# FE_Channel.net
KiCad netlist of a schematic drawn in Altium Designer
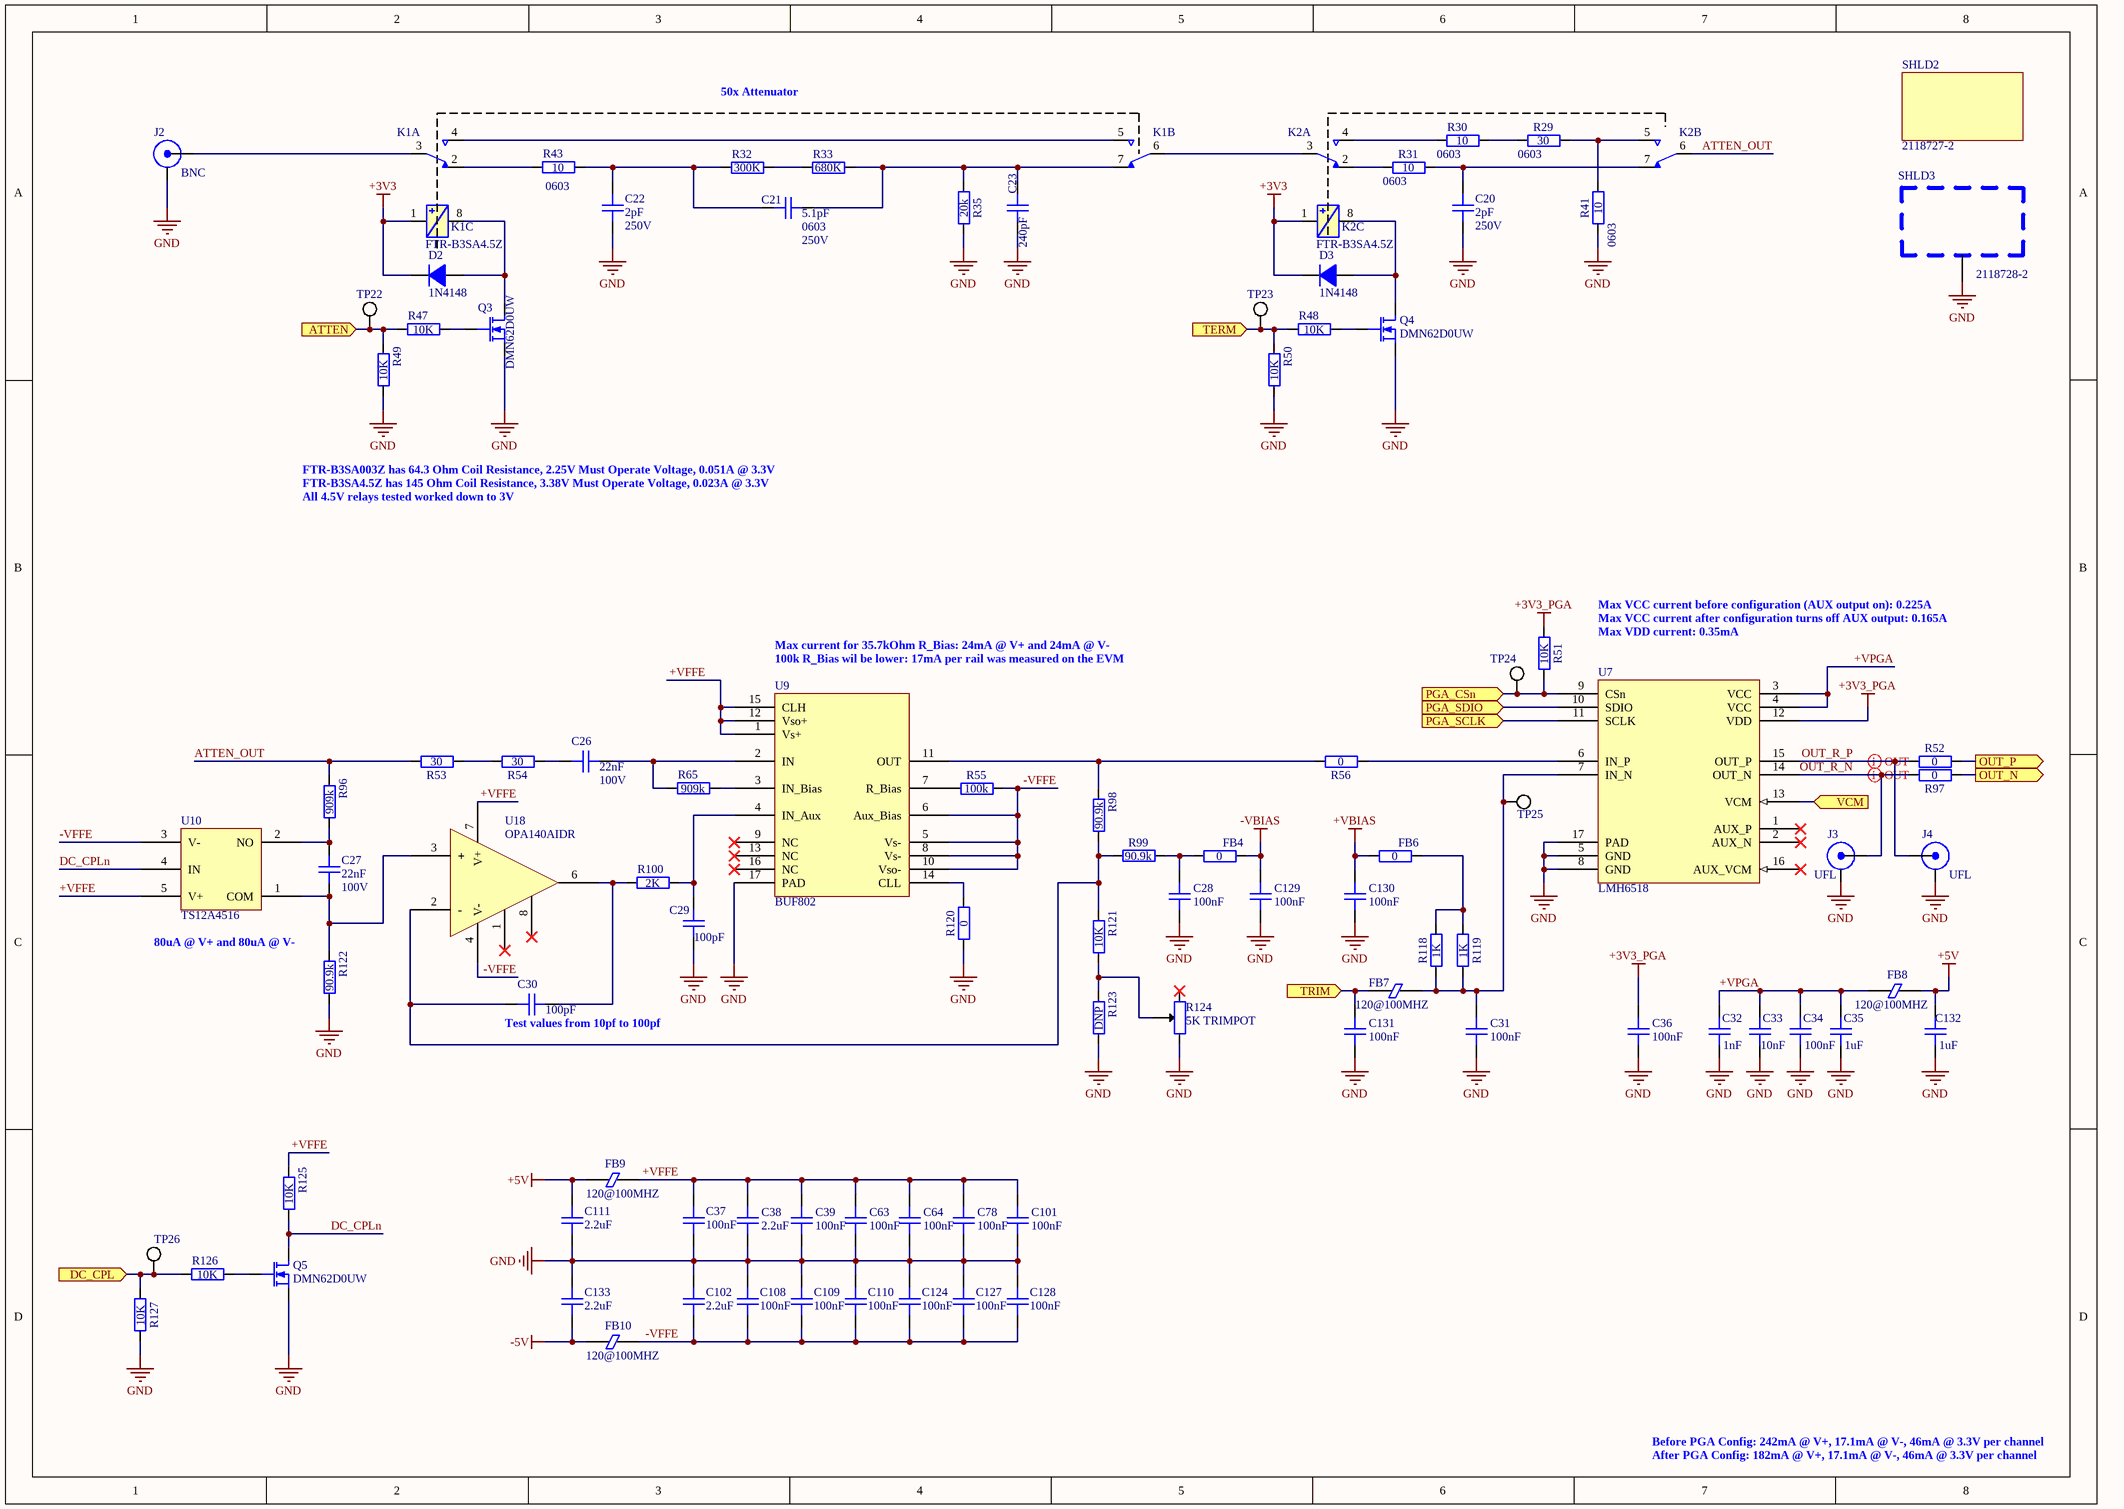
[diagram p0: FE_Channel.SchDoc]

(export (version "E")
  (design (tool "Eeschema 10.0.6"))
  (components
    (comp (ref "C20")
      (value "2pF")
      (footprint "GEN_C_0603")
      (fields
        (field (name "MANUFACTURER") "KEMET")
        (field (name "MANUFACTURER PART NUMBER") "CBR06C309BAGAC")
        (field (name "VOLTAGE RATING") "250V")
      )
      (libsource (lib "DSO") (part "CAP 2pF 250V C0G 0603"))
    )
    (comp (ref "C21")
      (value "5.1pF")
      (footprint "GEN_C_0603")
      (fields
        (field (name "PACKAGE") "0603")
        (field (name "VOLTAGE RATING") "250V")
        (field (name "MANUFACTURER") "KEMET")
        (field (name "MANUFACTURER PART NUMBER") "CBR06C519BAGAC")
      )
      (libsource (lib "DSO") (part "CAP 5.1pF 250V C0G 0603"))
    )
    (comp (ref "C22")
      (value "2pF")
      (footprint "GEN_C_0603")
      (fields
        (field (name "MANUFACTURER") "KEMET")
        (field (name "MANUFACTURER PART NUMBER") "CBR06C309BAGAC")
        (field (name "VOLTAGE RATING") "250V")
      )
      (libsource (lib "DSO") (part "CAP 2pF 250V C0G 0603"))
    )
    (comp (ref "C23")
      (value "240pF")
      (footprint "GEN_C_0805")
      (fields
        (field (name "MANUFACTURER") "Kyocera AVX")
        (field (name "MANUFACTURER PART NUMBER") "600F241FT250XT")
      )
      (libsource (lib "DSO") (part "CAP 240pF 250V C0G 0805"))
    )
    (comp (ref "C26")
      (value "22nF")
      (footprint "GEN_C_0603")
      (fields
        (field (name "VOLTAGE RATING") "100V")
        (field (name "MANUFACTURER") "Murata")
        (field (name "MANUFACTURER PART NUMBER") "GCM188R72A223KA37D")
      )
      (libsource (lib "DSO") (part "CAP 22nF 100V X7R 0603"))
    )
    (comp (ref "C27")
      (value "22nF")
      (footprint "GEN_C_0603")
      (fields
        (field (name "VOLTAGE RATING") "100V")
        (field (name "MANUFACTURER") "Murata")
        (field (name "MANUFACTURER PART NUMBER") "GCM188R72A223KA37D")
      )
      (libsource (lib "DSO") (part "CAP 22nF 100V X7R 0603"))
    )
    (comp (ref "C28")
      (value "100nF")
      (footprint "GEN_C_0402")
      (fields
        (field (name "HOUSE PART NUMBER") "C-100nF-0402-002")
        (field (name "MANUFACTURER") "Murata")
        (field (name "MANUFACTURER PART NUMBER") "GCM155R71C104KA55D")
      )
      (libsource (lib "DSO") (part "CAP 100nF 16V X7R 0402"))
    )
    (comp (ref "C29")
      (value "100pF")
      (footprint "GEN_C_0402")
      (fields
        (field (name "MANUFACTURER") "Murata")
        (field (name "MANUFACTURER PART NUMBER") "GCM1555C1H101FA16D")
      )
      (libsource (lib "DSO") (part "CAP 100pF 50V C0G 0402"))
    )
    (comp (ref "C30")
      (value "100pF")
      (footprint "GEN_C_0402")
      (fields
        (field (name "MANUFACTURER") "Murata")
        (field (name "MANUFACTURER PART NUMBER") "GCM1555C1H101FA16D")
      )
      (libsource (lib "DSO") (part "CAP 100pF 50V C0G 0402"))
    )
    (comp (ref "C31")
      (value "100nF")
      (footprint "GEN_C_0402")
      (fields
        (field (name "HOUSE PART NUMBER") "C-100nF-0402-002")
        (field (name "MANUFACTURER") "Murata")
        (field (name "MANUFACTURER PART NUMBER") "GCM155R71C104KA55D")
      )
      (libsource (lib "DSO") (part "CAP 100nF 16V X7R 0402"))
    )
    (comp (ref "C32")
      (value "1nF")
      (footprint "GEN_C_0402")
      (fields
        (field (name "MANUFACTURER") "Murata")
        (field (name "MANUFACTURER PART NUMBER") "GRM1555C1H102FA01D")
      )
      (libsource (lib "DSO") (part "CAP 1nF 50V C0G 0402"))
    )
    (comp (ref "C33")
      (value "10nF")
      (footprint "GEN_C_0402")
      (fields
        (field (name "HOUSE PART NUMBER") "C-10nF-0402-002")
        (field (name "MANUFACTURER") "Murata")
        (field (name "MANUFACTURER PART NUMBER") "GRM155R71H103KA88J")
      )
      (libsource (lib "DSO") (part "CAP 10nF 50V X7R 0402"))
    )
    (comp (ref "C34")
      (value "100nF")
      (footprint "GEN_C_0402")
      (fields
        (field (name "HOUSE PART NUMBER") "C-100nF-0402-002")
        (field (name "MANUFACTURER") "Murata")
        (field (name "MANUFACTURER PART NUMBER") "GCM155R71C104KA55D")
      )
      (libsource (lib "DSO") (part "CAP 100nF 16V X7R 0402"))
    )
    (comp (ref "C35")
      (value "1uF")
      (footprint "GEN_C_0402")
      (fields
        (field (name "MANUFACTURER") "Murata")
        (field (name "MANUFACTURER PART NUMBER") "GRM155R61E105KA12D")
      )
      (libsource (lib "DSO") (part "CAP 1uF 25V X5R 0402"))
    )
    (comp (ref "C36")
      (value "100nF")
      (footprint "GEN_C_0402")
      (fields
        (field (name "HOUSE PART NUMBER") "C-100nF-0402-002")
        (field (name "MANUFACTURER") "Murata")
        (field (name "MANUFACTURER PART NUMBER") "GCM155R71C104KA55D")
      )
      (libsource (lib "DSO") (part "CAP 100nF 16V X7R 0402"))
    )
    (comp (ref "C37")
      (value "100nF")
      (footprint "GEN_C_0402")
      (fields
        (field (name "MANUFACTURER") "Murata")
        (field (name "HOUSE PART NUMBER") "C-100nF-0402-002")
        (field (name "MANUFACTURER PART NUMBER") "GCM155R71C104KA55D")
      )
      (libsource (lib "DSO") (part "CAP 100nF 16V X7R 0402"))
    )
    (comp (ref "C38")
      (value "2.2uF")
      (footprint "GEN_C_0402")
      (fields
        (field (name "MANUFACTURER") "Taiyo Yuden")
        (field (name "MANUFACTURER PART NUMBER") "LMK105BJ225MV-F")
      )
      (libsource (lib "DSO") (part "CAP 2.2uF 10V X5R 0402"))
    )
    (comp (ref "C39")
      (value "100nF")
      (footprint "GEN_C_0402")
      (fields
        (field (name "HOUSE PART NUMBER") "C-100nF-0402-002")
        (field (name "MANUFACTURER") "Murata")
        (field (name "MANUFACTURER PART NUMBER") "GCM155R71C104KA55D")
      )
      (libsource (lib "DSO") (part "CAP 100nF 16V X7R 0402"))
    )
    (comp (ref "C63")
      (value "100nF")
      (footprint "GEN_C_0402")
      (fields
        (field (name "HOUSE PART NUMBER") "C-100nF-0402-002")
        (field (name "MANUFACTURER") "Murata")
        (field (name "MANUFACTURER PART NUMBER") "GCM155R71C104KA55D")
      )
      (libsource (lib "DSO") (part "CAP 100nF 16V X7R 0402"))
    )
    (comp (ref "C64")
      (value "100nF")
      (footprint "GEN_C_0402")
      (fields
        (field (name "HOUSE PART NUMBER") "C-100nF-0402-002")
        (field (name "MANUFACTURER") "Murata")
        (field (name "MANUFACTURER PART NUMBER") "GCM155R71C104KA55D")
      )
      (libsource (lib "DSO") (part "CAP 100nF 16V X7R 0402"))
    )
    (comp (ref "C78")
      (value "100nF")
      (footprint "GEN_C_0402")
      (fields
        (field (name "HOUSE PART NUMBER") "C-100nF-0402-002")
        (field (name "MANUFACTURER") "Murata")
        (field (name "MANUFACTURER PART NUMBER") "GCM155R71C104KA55D")
      )
      (libsource (lib "DSO") (part "CAP 100nF 16V X7R 0402"))
    )
    (comp (ref "C101")
      (value "100nF")
      (footprint "GEN_C_0402")
      (fields
        (field (name "HOUSE PART NUMBER") "C-100nF-0402-002")
        (field (name "MANUFACTURER") "Murata")
        (field (name "MANUFACTURER PART NUMBER") "GCM155R71C104KA55D")
      )
      (libsource (lib "DSO") (part "CAP 100nF 16V X7R 0402"))
    )
    (comp (ref "C102")
      (value "2.2uF")
      (footprint "GEN_C_0402")
      (fields
        (field (name "MANUFACTURER") "Taiyo Yuden")
        (field (name "MANUFACTURER PART NUMBER") "LMK105BJ225MV-F")
      )
      (libsource (lib "DSO") (part "CAP 2.2uF 10V X5R 0402"))
    )
    (comp (ref "C108")
      (value "100nF")
      (footprint "GEN_C_0402")
      (fields
        (field (name "HOUSE PART NUMBER") "C-100nF-0402-002")
        (field (name "MANUFACTURER") "Murata")
        (field (name "MANUFACTURER PART NUMBER") "GCM155R71C104KA55D")
      )
      (libsource (lib "DSO") (part "CAP 100nF 16V X7R 0402"))
    )
    (comp (ref "C109")
      (value "100nF")
      (footprint "GEN_C_0402")
      (fields
        (field (name "HOUSE PART NUMBER") "C-100nF-0402-002")
        (field (name "MANUFACTURER") "Murata")
        (field (name "MANUFACTURER PART NUMBER") "GCM155R71C104KA55D")
      )
      (libsource (lib "DSO") (part "CAP 100nF 16V X7R 0402"))
    )
    (comp (ref "C110")
      (value "100nF")
      (footprint "GEN_C_0402")
      (fields
        (field (name "HOUSE PART NUMBER") "C-100nF-0402-002")
        (field (name "MANUFACTURER") "Murata")
        (field (name "MANUFACTURER PART NUMBER") "GCM155R71C104KA55D")
      )
      (libsource (lib "DSO") (part "CAP 100nF 16V X7R 0402"))
    )
    (comp (ref "C111")
      (value "2.2uF")
      (footprint "GEN_C_0402")
      (fields
        (field (name "MANUFACTURER") "Taiyo Yuden")
        (field (name "MANUFACTURER PART NUMBER") "LMK105BJ225MV-F")
      )
      (libsource (lib "DSO") (part "CAP 2.2uF 10V X5R 0402"))
    )
    (comp (ref "C124")
      (value "100nF")
      (footprint "GEN_C_0402")
      (fields
        (field (name "HOUSE PART NUMBER") "C-100nF-0402-002")
        (field (name "MANUFACTURER") "Murata")
        (field (name "MANUFACTURER PART NUMBER") "GCM155R71C104KA55D")
      )
      (libsource (lib "DSO") (part "CAP 100nF 16V X7R 0402"))
    )
    (comp (ref "C127")
      (value "100nF")
      (footprint "GEN_C_0402")
      (fields
        (field (name "HOUSE PART NUMBER") "C-100nF-0402-002")
        (field (name "MANUFACTURER") "Murata")
        (field (name "MANUFACTURER PART NUMBER") "GCM155R71C104KA55D")
      )
      (libsource (lib "DSO") (part "CAP 100nF 16V X7R 0402"))
    )
    (comp (ref "C128")
      (value "100nF")
      (footprint "GEN_C_0402")
      (fields
        (field (name "HOUSE PART NUMBER") "C-100nF-0402-002")
        (field (name "MANUFACTURER") "Murata")
        (field (name "MANUFACTURER PART NUMBER") "GCM155R71C104KA55D")
      )
      (libsource (lib "DSO") (part "CAP 100nF 16V X7R 0402"))
    )
    (comp (ref "C129")
      (value "100nF")
      (footprint "GEN_C_0402")
      (fields
        (field (name "HOUSE PART NUMBER") "C-100nF-0402-002")
        (field (name "MANUFACTURER") "Murata")
        (field (name "MANUFACTURER PART NUMBER") "GCM155R71C104KA55D")
      )
      (libsource (lib "DSO") (part "CAP 100nF 16V X7R 0402"))
    )
    (comp (ref "C130")
      (value "100nF")
      (footprint "GEN_C_0402")
      (fields
        (field (name "HOUSE PART NUMBER") "C-100nF-0402-002")
        (field (name "MANUFACTURER") "Murata")
        (field (name "MANUFACTURER PART NUMBER") "GCM155R71C104KA55D")
      )
      (libsource (lib "DSO") (part "CAP 100nF 16V X7R 0402"))
    )
    (comp (ref "C131")
      (value "100nF")
      (footprint "GEN_C_0402")
      (fields
        (field (name "HOUSE PART NUMBER") "C-100nF-0402-002")
        (field (name "MANUFACTURER") "Murata")
        (field (name "MANUFACTURER PART NUMBER") "GCM155R71C104KA55D")
      )
      (libsource (lib "DSO") (part "CAP 100nF 16V X7R 0402"))
    )
    (comp (ref "C132")
      (value "1uF")
      (footprint "GEN_C_0402")
      (fields
        (field (name "MANUFACTURER") "Murata")
        (field (name "MANUFACTURER PART NUMBER") "GRM155R61E105KA12D")
      )
      (libsource (lib "DSO") (part "CAP 1uF 25V X5R 0402"))
    )
    (comp (ref "C133")
      (value "2.2uF")
      (footprint "GEN_C_0402")
      (fields
        (field (name "MANUFACTURER") "Taiyo Yuden")
        (field (name "MANUFACTURER PART NUMBER") "LMK105BJ225MV-F")
      )
      (libsource (lib "DSO") (part "CAP 2.2uF 10V X5R 0402"))
    )
    (comp (ref "D2")
      (value "1N4148")
      (footprint "GEN_SOD_323")
      (fields (field (name "MANUFACTURER") "Diodes") (field (name "MANUFACTURER PART NUMBER") "1N4148WS-7-F"))
      (libsource (lib "DSO") (part "DIODE 1N4148"))
    )
    (comp (ref "D3")
      (value "1N4148")
      (footprint "GEN_SOD_323")
      (fields (field (name "MANUFACTURER") "Diodes") (field (name "MANUFACTURER PART NUMBER") "1N4148WS-7-F"))
      (libsource (lib "DSO") (part "DIODE 1N4148"))
    )
    (comp (ref "FB4")
      (value "0")
      (footprint "GEN_R_0402")
      (fields
        (field (name "MANUFACTURER") "Yageo")
        (field (name "MANUFACTURER PART NUMBER") "RC0402JR-070RL")
      )
      (libsource (lib "DSO") (part "RES 0 OHM 1/16W 0402"))
    )
    (comp (ref "FB6")
      (value "0")
      (footprint "GEN_R_0402")
      (fields
        (field (name "MANUFACTURER") "Yageo")
        (field (name "MANUFACTURER PART NUMBER") "RC0402JR-070RL")
      )
      (libsource (lib "DSO") (part "RES 0 OHM 1/16W 0402"))
    )
    (comp (ref "FB7")
      (value "120@100MHZ")
      (footprint "GEN_R_0402")
      (fields (field (name "HOUSE PART NUMBER") "BLM15PX121SN1D") (field (name "MANUFACTURER") "Murata"))
      (libsource (lib "DSO") (part "FERRITE BEAD 120 OHM 0402"))
    )
    (comp (ref "FB8")
      (value "120@100MHZ")
      (footprint "GEN_R_0402")
      (fields (field (name "HOUSE PART NUMBER") "BLM15PX121SN1D") (field (name "MANUFACTURER") "Murata"))
      (libsource (lib "DSO") (part "FERRITE BEAD 120 OHM 0402"))
    )
    (comp (ref "FB9")
      (value "120@100MHZ")
      (footprint "GEN_R_0402")
      (fields (field (name "HOUSE PART NUMBER") "BLM15PX121SN1D") (field (name "MANUFACTURER") "Murata"))
      (libsource (lib "DSO") (part "FERRITE BEAD 120 OHM 0402"))
    )
    (comp (ref "FB10")
      (value "120@100MHZ")
      (footprint "GEN_R_0402")
      (fields (field (name "HOUSE PART NUMBER") "BLM15PX121SN1D") (field (name "MANUFACTURER") "Murata"))
      (libsource (lib "DSO") (part "FERRITE BEAD 120 OHM 0402"))
    )
    (comp (ref "J2")
      (value "BNC")
      (footprint "MOL_0731000105")
      (fields (field (name "MANUFACTURER") "Molex") (field (name "MANUFACTURER PART NUMBER") "73100-0105"))
      (libsource (lib "DSO") (part "BNC JACK R/A"))
    )
    (comp (ref "J3")
      (value "UFL")
      (footprint "TE_2334884-1")
      (fields
        (field (name "MANUFACTURER") "TE Connectivity")
        (field (name "MANUFACTURER PART NUMBER") "2334884-1")
      )
      (libsource (lib "DSO") (part "UFL Jack SMD"))
    )
    (comp (ref "J4")
      (value "UFL")
      (footprint "TE_2334884-1")
      (fields
        (field (name "MANUFACTURER") "TE Connectivity")
        (field (name "MANUFACTURER PART NUMBER") "2334884-1")
      )
      (libsource (lib "DSO") (part "UFL Jack SMD"))
    )
    (comp (ref "K1")
      (value "FTR-B3SA4.5Z")
      (footprint "FUJ_FTR-B3SA")
      (fields (field (name "MANUFACTURER") "Fujitsu"))
      (libsource (lib "") (part "RELAY DPDT-NO FTR-B3SA4.5Z_1"))
    )
    (comp (ref "K2")
      (value "FTR-B3SA4.5Z")
      (footprint "FUJ_FTR-B3SA")
      (fields (field (name "MANUFACTURER") "Fujitsu"))
      (libsource (lib "") (part "RELAY DPDT-NO FTR-B3SA4.5Z_1"))
    )
    (comp (ref "Q3")
      (value "DMN62D0UW")
      (footprint "GEN_SOT_323")
      (fields (field (name "HOUSE PART NUMBER") "DMN62D0UW-7") (field (name "MANUFACTURER") "Diodes"))
      (libsource (lib "DSO") (part "NMOS DMN62D0UW"))
    )
    (comp (ref "Q4")
      (value "DMN62D0UW")
      (footprint "GEN_SOT_323")
      (fields (field (name "HOUSE PART NUMBER") "DMN62D0UW-7") (field (name "MANUFACTURER") "Diodes"))
      (libsource (lib "DSO") (part "NMOS DMN62D0UW"))
    )
    (comp (ref "Q5")
      (value "DMN62D0UW")
      (footprint "GEN_SOT_323")
      (fields (field (name "HOUSE PART NUMBER") "DMN62D0UW-7") (field (name "MANUFACTURER") "Diodes"))
      (libsource (lib "DSO") (part "NMOS DMN62D0UW"))
    )
    (comp (ref "R29")
      (value "30")
      (footprint "GEN_R_0603")
      (fields
        (field (name "TOLERANCE") "1%")
        (field (name "PACKAGE") "0603")
        (field (name "MANUFACTURER") "KOA Speer")
        (field (name "MANUFACTURER PART NUMBER") "SG73P1JTTD30R0F")
      )
      (libsource (lib "DSO") (part "RES 30 OHM 1% 1/3W 0603"))
    )
    (comp (ref "R30")
      (value "10")
      (footprint "GEN_R_0603")
      (fields
        (field (name "PACKAGE") "0603")
        (field (name "TOLERANCE") "1%")
        (field (name "MANUFACTURER") "KOA Speer")
        (field (name "MANUFACTURER PART NUMBER") "SG73P1JTTD10R0F")
      )
      (libsource (lib "") (part "RES 10 OHM 1% 1/3W 0603_1"))
    )
    (comp (ref "R31")
      (value "10")
      (footprint "GEN_R_0603")
      (fields
        (field (name "TOLERANCE") "1%")
        (field (name "PACKAGE") "0603")
        (field (name "MANUFACTURER") "KOA Speer")
        (field (name "MANUFACTURER PART NUMBER") "SG73P1JTTD10R0F")
      )
      (libsource (lib "") (part "RES 10 OHM 1% 1/3W 0603_1"))
    )
    (comp (ref "R32")
      (value "300K")
      (footprint "GEN_R_0402")
      (fields
        (field (name "TOLERANCE") "1%")
        (field (name "MANUFACTURER") "Panasonic")
        (field (name "MANUFACTURER PART NUMBER") "ERJ-2RKF3003X")
      )
      (libsource (lib "DSO") (part "RES 300K OHM 1% 1/10W 0402"))
    )
    (comp (ref "R33")
      (value "680K")
      (footprint "GEN_R_0402")
      (fields
        (field (name "TOLERANCE") "1%")
        (field (name "MANUFACTURER") "Yageo")
        (field (name "MANUFACTURER PART NUMBER") "RC0402FR-07681KL")
      )
      (libsource (lib "DSO") (part "RES 680K OHM 1% 1/16W 0402"))
    )
    (comp (ref "R35")
      (value "20k")
      (footprint "GEN_R_0402")
      (fields
        (field (name "TOLERANCE") "1%")
        (field (name "MANUFACTURER") "Yageo")
        (field (name "MANUFACTURER PART NUMBER") "RC0402FR-0720KL")
      )
      (libsource (lib "DSO") (part "RES 20K OHM 1% 1/16W 0402"))
    )
    (comp (ref "R41")
      (value "10")
      (footprint "GEN_R_0603")
      (fields
        (field (name "TOLERANCE") "1%")
        (field (name "PACKAGE") "0603")
        (field (name "MANUFACTURER") "KOA Speer")
        (field (name "MANUFACTURER PART NUMBER") "SG73P1JTTD10R0F")
      )
      (libsource (lib "") (part "RES 10 OHM 1% 1/3W 0603_2"))
    )
    (comp (ref "R43")
      (value "10")
      (footprint "GEN_R_0603")
      (fields
        (field (name "TOLERANCE") "1%")
        (field (name "PACKAGE") "0603")
        (field (name "MANUFACTURER") "KOA Speer")
        (field (name "MANUFACTURER PART NUMBER") "SG73P1JTTD10R0F")
      )
      (libsource (lib "DSO") (part "RES 10 OHM 1% 1/3W 0603"))
    )
    (comp (ref "R47")
      (value "10K")
      (footprint "GEN_R_0402")
      (fields
        (field (name "TOLERANCE") "1%")
        (field (name "MANUFACTURER") "Panasonic")
        (field (name "MANUFACTURER PART NUMBER") "ERJ-2RKF1002X")
      )
      (libsource (lib "DSO") (part "RES 10K OHM 1% 1/10W 0402"))
    )
    (comp (ref "R48")
      (value "10K")
      (footprint "GEN_R_0402")
      (fields
        (field (name "TOLERANCE") "1%")
        (field (name "MANUFACTURER") "Panasonic")
        (field (name "MANUFACTURER PART NUMBER") "ERJ-2RKF1002X")
      )
      (libsource (lib "DSO") (part "RES 10K OHM 1% 1/10W 0402"))
    )
    (comp (ref "R49")
      (value "10K")
      (footprint "GEN_R_0402")
      (fields
        (field (name "TOLERANCE") "1%")
        (field (name "MANUFACTURER") "Panasonic")
        (field (name "MANUFACTURER PART NUMBER") "ERJ-2RKF1002X")
      )
      (libsource (lib "") (part "RES 10K OHM 1% 1/10W 0402_1"))
    )
    (comp (ref "R50")
      (value "10K")
      (footprint "GEN_R_0402")
      (fields
        (field (name "TOLERANCE") "1%")
        (field (name "MANUFACTURER") "Panasonic")
        (field (name "MANUFACTURER PART NUMBER") "ERJ-2RKF1002X")
      )
      (libsource (lib "") (part "RES 10K OHM 1% 1/10W 0402_1"))
    )
    (comp (ref "R51")
      (value "10K")
      (footprint "GEN_R_0402")
      (fields
        (field (name "TOLERANCE") "1%")
        (field (name "MANUFACTURER") "Panasonic")
        (field (name "MANUFACTURER PART NUMBER") "ERJ-2RKF1002X")
      )
      (libsource (lib "") (part "RES 10K OHM 1% 1/10W 0402_1"))
    )
    (comp (ref "R52")
      (value "0")
      (footprint "GEN_R_0402")
      (fields
        (field (name "MANUFACTURER") "Yageo")
        (field (name "MANUFACTURER PART NUMBER") "RC0402JR-070RL")
      )
      (libsource (lib "DSO") (part "RES 0 OHM 1/16W 0402"))
    )
    (comp (ref "R53")
      (value "30")
      (footprint "GEN_R_0603")
      (fields
        (field (name "TOLERANCE") "1%")
        (field (name "MANUFACTURER") "KOA Speer")
        (field (name "MANUFACTURER PART NUMBER") "SG73P1JTTD30R0F")
      )
      (libsource (lib "DSO") (part "RES 30 OHM 1% 1/3W 0603"))
    )
    (comp (ref "R54")
      (value "30")
      (footprint "GEN_R_0603")
      (fields
        (field (name "TOLERANCE") "1%")
        (field (name "MANUFACTURER") "KOA Speer")
        (field (name "MANUFACTURER PART NUMBER") "SG73P1JTTD30R0F")
      )
      (libsource (lib "DSO") (part "RES 30 OHM 1% 1/3W 0603"))
    )
    (comp (ref "R55")
      (value "100k")
      (footprint "GEN_R_0402")
      (fields
        (field (name "TOLERANCE") "1%")
        (field (name "HOUSE PART NUMBER") "R-100K-0402-1%-001")
        (field (name "MANUFACTURER") "Yageo")
      )
      (libsource (lib "DSO") (part "RES 100K OHM 1% 1/10W 0402"))
    )
    (comp (ref "R56")
      (value "0")
      (footprint "GEN_R_0402")
      (fields
        (field (name "MANUFACTURER") "Yageo")
        (field (name "MANUFACTURER PART NUMBER") "RC0402JR-070RL")
      )
      (libsource (lib "DSO") (part "RES 0 OHM 1/16W 0402"))
    )
    (comp (ref "R65")
      (value "909k")
      (footprint "GEN_R_0402")
      (fields
        (field (name "TOLERANCE") "1%")
        (field (name "MANUFACTURER") "Yageo")
        (field (name "MANUFACTURER PART NUMBER") "RC0402FR-07909KL")
      )
      (libsource (lib "") (part "RES 909K OHM 1% 1/16W 0402_1"))
    )
    (comp (ref "R96")
      (value "909k")
      (footprint "GEN_R_0402")
      (fields
        (field (name "TOLERANCE") "1%")
        (field (name "MANUFACTURER") "Yageo")
        (field (name "MANUFACTURER PART NUMBER") "RC0402FR-07909KL")
      )
      (libsource (lib "DSO") (part "RES 909K OHM 1% 1/16W 0402"))
    )
    (comp (ref "R97")
      (value "0")
      (footprint "GEN_R_0402")
      (fields
        (field (name "MANUFACTURER") "Yageo")
        (field (name "MANUFACTURER PART NUMBER") "RC0402JR-070RL")
      )
      (libsource (lib "DSO") (part "RES 0 OHM 1/16W 0402"))
    )
    (comp (ref "R98")
      (value "90.9k")
      (footprint "GEN_R_0402")
      (fields
        (field (name "TOLERANCE") "1%")
        (field (name "MANUFACTURER") "Yageo")
        (field (name "MANUFACTURER PART NUMBER") "RC0402FR-0790K9L")
      )
      (libsource (lib "DSO") (part "RES 90.9K OHM 1% 1/16W 0402"))
    )
    (comp (ref "R99")
      (value "90.9k")
      (footprint "GEN_R_0402")
      (fields
        (field (name "TOLERANCE") "1%")
        (field (name "MANUFACTURER") "Yageo")
        (field (name "MANUFACTURER PART NUMBER") "RC0402FR-0790K9L")
      )
      (libsource (lib "") (part "RES 90.9K OHM 1% 1/16W 0402_1"))
    )
    (comp (ref "R100")
      (value "2K")
      (footprint "GEN_R_0402")
      (fields
        (field (name "TOLERANCE") "1%")
        (field (name "MANUFACTURER") "Yageo")
        (field (name "MANUFACTURER PART NUMBER") "RC0402FR-072KL")
      )
      (libsource (lib "DSO") (part "RES 2K OHM 1% 1/16W 0402"))
    )
    (comp (ref "R118")
      (value "1K")
      (footprint "GEN_R_0402")
      (fields
        (field (name "TOLERANCE") "1%")
        (field (name "HOUSE PART NUMBER") "R-1K-0402-1%-001")
        (field (name "MANUFACTURER") "Yageo")
      )
      (libsource (lib "") (part "RES 1K OHM 1% 1/10W 0402_1"))
    )
    (comp (ref "R119")
      (value "1K")
      (footprint "GEN_R_0402")
      (fields
        (field (name "TOLERANCE") "1%")
        (field (name "HOUSE PART NUMBER") "R-1K-0402-1%-001")
        (field (name "MANUFACTURER") "Yageo")
      )
      (libsource (lib "DSO") (part "RES 1K OHM 1% 1/10W 0402"))
    )
    (comp (ref "R120")
      (value "0")
      (footprint "GEN_R_0402")
      (fields
        (field (name "MANUFACTURER") "Yageo")
        (field (name "MANUFACTURER PART NUMBER") "RC0402JR-070RL")
      )
      (libsource (lib "") (part "RES 0 OHM 1/16W 0402_1"))
    )
    (comp (ref "R121")
      (value "10K")
      (footprint "GEN_R_0402")
      (fields
        (field (name "TOLERANCE") "1%")
        (field (name "MANUFACTURER") "Panasonic")
        (field (name "MANUFACTURER PART NUMBER") "ERJ-2RKF1002X")
      )
      (libsource (lib "") (part "RES 10K OHM 1% 1/10W 0402_1"))
    )
    (comp (ref "R122")
      (value "90.9k")
      (footprint "GEN_R_0402")
      (fields
        (field (name "TOLERANCE") "1%")
        (field (name "MANUFACTURER") "Yageo")
        (field (name "MANUFACTURER PART NUMBER") "RC0402FR-0790K9L")
      )
      (libsource (lib "DSO") (part "RES 90.9K OHM 1% 1/16W 0402"))
    )
    (comp (ref "R123")
      (value "DNP")
      (footprint "GEN_R_0402")
      (fields (field (name "TOLERANCE") "1%"))
      (libsource (lib "DSO") (part "RES DNP 0402"))
    )
    (comp (ref "R124")
      (value "5K TRIMPOT")
      (footprint "BOU_3mm_POT")
      (fields
        (field (name "TOLERANCE") "1%")
        (field (name "MANUFACTURER") "Bourns")
        (field (name "MANUFACTURER PART NUMBER") "TC33X-2-502E")
      )
      (libsource (lib "DSO") (part "TRIMMER 5K OHM 0.1W J LEAD TOP"))
    )
    (comp (ref "R125")
      (value "10K")
      (footprint "GEN_R_0402")
      (fields
        (field (name "TOLERANCE") "1%")
        (field (name "MANUFACTURER") "Panasonic")
        (field (name "MANUFACTURER PART NUMBER") "ERJ-2RKF1002X")
      )
      (libsource (lib "") (part "RES 10K OHM 1% 1/10W 0402_1"))
    )
    (comp (ref "R126")
      (value "10K")
      (footprint "GEN_R_0402")
      (fields
        (field (name "TOLERANCE") "1%")
        (field (name "MANUFACTURER") "Panasonic")
        (field (name "MANUFACTURER PART NUMBER") "ERJ-2RKF1002X")
      )
      (libsource (lib "DSO") (part "RES 10K OHM 1% 1/10W 0402"))
    )
    (comp (ref "R127")
      (value "10K")
      (footprint "GEN_R_0402")
      (fields
        (field (name "TOLERANCE") "1%")
        (field (name "MANUFACTURER") "Panasonic")
        (field (name "MANUFACTURER PART NUMBER") "ERJ-2RKF1002X")
      )
      (libsource (lib "") (part "RES 10K OHM 1% 1/10W 0402_2"))
    )
    (comp (ref "SHLD2")
      (value "2118727-2")
      (fields (field (name "MANUFACTURER") "TE Connectivity AMP"))
      (libsource (lib "DSO") (part "SHIELD 2118727-2"))
    )
    (comp (ref "SHLD3")
      (value "2118728-2")
      (footprint "TE_2118728-2")
      (fields (field (name "MANUFACTURER") "TE Connectivity"))
      (libsource (lib "DSO") (part "SHIELD 2118728-2"))
    )
    (comp (ref "TP22") (value "PCB") (footprint "GEN_TP_PCB") (libsource (lib "DSO") (part "TP PCB 1mm")))
    (comp (ref "TP23") (value "PCB") (footprint "GEN_TP_PCB") (libsource (lib "DSO") (part "TP PCB 1mm")))
    (comp (ref "TP24") (value "PCB") (footprint "GEN_TP_PCB") (libsource (lib "DSO") (part "TP PCB 1mm")))
    (comp (ref "TP25") (value "PCB") (footprint "GEN_TP_PCB") (libsource (lib "DSO") (part "TP PCB 1mm")))
    (comp (ref "TP26") (value "PCB") (footprint "GEN_TP_PCB") (libsource (lib "DSO") (part "TP PCB 1mm")))
    (comp (ref "U7")
      (value "LMH6518")
      (footprint "TI_WQFN_RGH0016A")
      (fields
        (field (name "MANUFACTURER") "Texas Instruments")
        (field (name "MANUFACTURER PART NUMBER") "LMH6518SQE/NOPB")
      )
      (libsource (lib "DSO") (part "IC PGA LMH6518"))
    )
    (comp (ref "U9")
      (value "BUF802")
      (footprint "TI_VQFN_RGT0016C")
      (fields
        (field (name "MANUFACTURER") "Texas Instruments")
        (field (name "MANUFACTURER PART NUMBER") "BUF802IRGTR")
      )
      (libsource (lib "DSO") (part "IC BUFFER AMP BUF802"))
    )
    (comp (ref "U10")
      (value "TS12A4516")
      (footprint "GEN_SOT23_5_950_2900X1600X1450")
      (fields
        (field (name "MANUFACTURER") "Texas Instruments")
        (field (name "MANUFACTURER PART NUMBER") "TS12A4516DBVR")
      )
      (libsource (lib "DSO") (part "IC SWITCH SPST TS12A4516DBVR"))
    )
    (comp (ref "U18")
      (value "OPA140AIDR")
      (footprint "TI_SOIC8_D0008A")
      (fields (field (name "MANUFACTURER") "Texas Instruments"))
      (libsource (lib "DSO") (part "IC OPAMP OPA140"))
    )
  )
  (nets
    (net (code "1") (name "+3V3") (class "Default")
      (node (ref "D2") (pin "1") (pinfunction "K_1") (pintype "passive"))
      (node (ref "D3") (pin "1") (pinfunction "K_1") (pintype "passive"))
      (node (ref "K1") (pin "1") (pinfunction "1_1") (pintype "passive"))
      (node (ref "K2") (pin "1") (pinfunction "1_1") (pintype "passive"))
    )
    (net (code "2") (name "+3V3_PGA") (class "Default")
      (node (ref "C36") (pin "2") (pinfunction "2_2") (pintype "passive"))
      (node (ref "R51") (pin "2") (pinfunction "2_2") (pintype "passive"))
      (node (ref "U7") (pin "12") (pinfunction "VDD_12") (pintype "power_in"))
    )
    (net (code "3") (name "+5V") (class "Default")
      (node (ref "C111") (pin "2") (pinfunction "2_2") (pintype "passive"))
      (node (ref "C132") (pin "2") (pinfunction "2_2") (pintype "passive"))
      (node (ref "FB8") (pin "2") (pinfunction "2_2") (pintype "passive"))
      (node (ref "FB9") (pin "1") (pinfunction "1_1") (pintype "passive"))
    )
    (net (code "4") (name "+VBIAS") (class "Default")
      (node (ref "C130") (pin "1") (pinfunction "1_1") (pintype "passive"))
      (node (ref "FB6") (pin "1") (pinfunction "1_1") (pintype "passive"))
    )
    (net (code "5") (name "-5V") (class "Default")
      (node (ref "C133") (pin "1") (pinfunction "1_1") (pintype "passive"))
      (node (ref "FB10") (pin "1") (pinfunction "1_1") (pintype "passive"))
    )
    (net (code "6") (name "-VBIAS") (class "Default")
      (node (ref "C129") (pin "1") (pinfunction "1_1") (pintype "passive"))
      (node (ref "FB4") (pin "2") (pinfunction "2_2") (pintype "passive"))
    )
    (net (code "7") (name "/+VFFE") (class "Default")
      (node (ref "C101") (pin "2") (pinfunction "2_2") (pintype "passive"))
      (node (ref "C37") (pin "2") (pinfunction "2_2") (pintype "passive"))
      (node (ref "C38") (pin "1") (pinfunction "1_1") (pintype "passive"))
      (node (ref "C39") (pin "1") (pinfunction "1_1") (pintype "passive"))
      (node (ref "C63") (pin "1") (pinfunction "1_1") (pintype "passive"))
      (node (ref "C64") (pin "2") (pinfunction "2_2") (pintype "passive"))
      (node (ref "C78") (pin "2") (pinfunction "2_2") (pintype "passive"))
      (node (ref "FB9") (pin "2") (pinfunction "2_2") (pintype "passive"))
      (node (ref "R125") (pin "2") (pinfunction "2_2") (pintype "passive"))
      (node (ref "U10") (pin "5") (pinfunction "V+_5") (pintype "passive"))
      (node (ref "U18") (pin "7") (pinfunction "V+_7") (pintype "passive"))
      (node (ref "U9") (pin "1") (pinfunction "Vs+_1") (pintype "passive"))
      (node (ref "U9") (pin "12") (pinfunction "Vso+_12") (pintype "passive"))
      (node (ref "U9") (pin "15") (pinfunction "CLH_15") (pintype "passive"))
    )
    (net (code "8") (name "/+VPGA") (class "Default")
      (node (ref "C32") (pin "2") (pinfunction "2_2") (pintype "passive"))
      (node (ref "C33") (pin "2") (pinfunction "2_2") (pintype "passive"))
      (node (ref "C34") (pin "2") (pinfunction "2_2") (pintype "passive"))
      (node (ref "C35") (pin "2") (pinfunction "2_2") (pintype "passive"))
      (node (ref "FB8") (pin "1") (pinfunction "1_1") (pintype "passive"))
      (node (ref "U7") (pin "3") (pinfunction "VCC_3") (pintype "power_in"))
      (node (ref "U7") (pin "4") (pinfunction "VCC_4") (pintype "power_in"))
    )
    (net (code "9") (name "/-VFFE") (class "Default")
      (node (ref "C102") (pin "2") (pinfunction "2_2") (pintype "passive"))
      (node (ref "C108") (pin "2") (pinfunction "2_2") (pintype "passive"))
      (node (ref "C109") (pin "1") (pinfunction "1_1") (pintype "passive"))
      (node (ref "C110") (pin "1") (pinfunction "1_1") (pintype "passive"))
      (node (ref "C124") (pin "1") (pinfunction "1_1") (pintype "passive"))
      (node (ref "C127") (pin "2") (pinfunction "2_2") (pintype "passive"))
      (node (ref "C128") (pin "2") (pinfunction "2_2") (pintype "passive"))
      (node (ref "FB10") (pin "2") (pinfunction "2_2") (pintype "passive"))
      (node (ref "R55") (pin "2") (pinfunction "2_2") (pintype "passive"))
      (node (ref "U10") (pin "3") (pinfunction "V-_3") (pintype "passive"))
      (node (ref "U18") (pin "4") (pinfunction "V-_4") (pintype "passive"))
      (node (ref "U9") (pin "10") (pinfunction "Vso-_10") (pintype "passive"))
      (node (ref "U9") (pin "5") (pinfunction "Vs-_5") (pintype "passive"))
      (node (ref "U9") (pin "6") (pinfunction "Aux_Bias_6") (pintype "passive"))
      (node (ref "U9") (pin "8") (pinfunction "Vs-_8") (pintype "passive"))
    )
    (net (code "10") (name "/ATTEN") (class "Default")
      (node (ref "R47") (pin "2") (pinfunction "2_2") (pintype "passive"))
      (node (ref "R49") (pin "2") (pinfunction "2_2") (pintype "passive"))
      (node (ref "TP22") (pin "1") (pinfunction "1_1") (pintype "passive"))
    )
    (net (code "11") (name "/ATTEN_OUT") (class "Default")
      (node (ref "K2") (pin "6") (pinfunction "6_6") (pintype "passive"))
      (node (ref "R53") (pin "1") (pinfunction "1_1") (pintype "passive"))
      (node (ref "R96") (pin "2") (pinfunction "2_2") (pintype "passive"))
    )
    (net (code "12") (name "/DC_CPL") (class "Default")
      (node (ref "R126") (pin "2") (pinfunction "2_2") (pintype "passive"))
      (node (ref "R127") (pin "2") (pinfunction "2_2") (pintype "passive"))
      (node (ref "TP26") (pin "1") (pinfunction "1_1") (pintype "passive"))
    )
    (net (code "13") (name "/DC_CPLn") (class "Default")
      (node (ref "Q5") (pin "1") (pinfunction "D_1") (pintype "passive"))
      (node (ref "R125") (pin "1") (pinfunction "1_1") (pintype "passive"))
      (node (ref "U10") (pin "4") (pinfunction "IN_4") (pintype "passive"))
    )
    (net (code "14") (name "/OUT_N") (class "Default")
      (node (ref "R97") (pin "2") (pinfunction "2_2") (pintype "passive"))
    )
    (net (code "15") (name "/OUT_P") (class "Default")
      (node (ref "R52") (pin "2") (pinfunction "2_2") (pintype "passive"))
    )
    (net (code "16") (name "/OUT_R_N") (class "Default")
      (node (ref "J3") (pin "1") (pinfunction "Signal_1") (pintype "passive"))
      (node (ref "R97") (pin "1") (pinfunction "1_1") (pintype "passive"))
      (node (ref "U7") (pin "14") (pinfunction "OUT_N_14") (pintype "passive"))
    )
    (net (code "17") (name "/OUT_R_P") (class "Default")
      (node (ref "J4") (pin "1") (pinfunction "Signal_1") (pintype "passive"))
      (node (ref "R52") (pin "1") (pinfunction "1_1") (pintype "passive"))
      (node (ref "U7") (pin "15") (pinfunction "OUT_P_15") (pintype "passive"))
    )
    (net (code "18") (name "/PGA_CSn") (class "Default")
      (node (ref "R51") (pin "1") (pinfunction "1_1") (pintype "passive"))
      (node (ref "TP24") (pin "1") (pinfunction "1_1") (pintype "passive"))
      (node (ref "U7") (pin "9") (pinfunction "CSn_9") (pintype "passive"))
    )
    (net (code "19") (name "/PGA_SCLK") (class "Default")
      (node (ref "U7") (pin "11") (pinfunction "SCLK_11") (pintype "passive"))
    )
    (net (code "20") (name "/PGA_SDIO") (class "Default")
      (node (ref "U7") (pin "10") (pinfunction "SDIO_10") (pintype "passive"))
    )
    (net (code "21") (name "/TERM") (class "Default")
      (node (ref "R48") (pin "2") (pinfunction "2_2") (pintype "passive"))
      (node (ref "R50") (pin "2") (pinfunction "2_2") (pintype "passive"))
      (node (ref "TP23") (pin "1") (pinfunction "1_1") (pintype "passive"))
    )
    (net (code "22") (name "/TRIM") (class "Default")
      (node (ref "C131") (pin "1") (pinfunction "1_1") (pintype "passive"))
      (node (ref "FB7") (pin "1") (pinfunction "1_1") (pintype "passive"))
    )
    (net (code "23") (name "/VCM") (class "Default")
      (node (ref "U7") (pin "13") (pinfunction "VCM_13") (pintype "input"))
    )
    (net (code "24") (name "GND") (class "Default")
      (node (ref "C101") (pin "1") (pinfunction "1_1") (pintype "passive"))
      (node (ref "C102") (pin "1") (pinfunction "1_1") (pintype "passive"))
      (node (ref "C108") (pin "1") (pinfunction "1_1") (pintype "passive"))
      (node (ref "C109") (pin "2") (pinfunction "2_2") (pintype "passive"))
      (node (ref "C110") (pin "2") (pinfunction "2_2") (pintype "passive"))
      (node (ref "C111") (pin "1") (pinfunction "1_1") (pintype "passive"))
      (node (ref "C124") (pin "2") (pinfunction "2_2") (pintype "passive"))
      (node (ref "C127") (pin "1") (pinfunction "1_1") (pintype "passive"))
      (node (ref "C128") (pin "1") (pinfunction "1_1") (pintype "passive"))
      (node (ref "C129") (pin "2") (pinfunction "2_2") (pintype "passive"))
      (node (ref "C130") (pin "2") (pinfunction "2_2") (pintype "passive"))
      (node (ref "C131") (pin "2") (pinfunction "2_2") (pintype "passive"))
      (node (ref "C132") (pin "1") (pinfunction "1_1") (pintype "passive"))
      (node (ref "C133") (pin "2") (pinfunction "2_2") (pintype "passive"))
      (node (ref "C20") (pin "2") (pinfunction "2_2") (pintype "passive"))
      (node (ref "C22") (pin "1") (pinfunction "1_1") (pintype "passive"))
      (node (ref "C23") (pin "1") (pinfunction "1_1") (pintype "passive"))
      (node (ref "C28") (pin "2") (pinfunction "2_2") (pintype "passive"))
      (node (ref "C29") (pin "1") (pinfunction "1_1") (pintype "passive"))
      (node (ref "C31") (pin "2") (pinfunction "2_2") (pintype "passive"))
      (node (ref "C32") (pin "1") (pinfunction "1_1") (pintype "passive"))
      (node (ref "C33") (pin "1") (pinfunction "1_1") (pintype "passive"))
      (node (ref "C34") (pin "1") (pinfunction "1_1") (pintype "passive"))
      (node (ref "C35") (pin "1") (pinfunction "1_1") (pintype "passive"))
      (node (ref "C36") (pin "1") (pinfunction "1_1") (pintype "passive"))
      (node (ref "C37") (pin "1") (pinfunction "1_1") (pintype "passive"))
      (node (ref "C38") (pin "2") (pinfunction "2_2") (pintype "passive"))
      (node (ref "C39") (pin "2") (pinfunction "2_2") (pintype "passive"))
      (node (ref "C63") (pin "2") (pinfunction "2_2") (pintype "passive"))
      (node (ref "C64") (pin "1") (pinfunction "1_1") (pintype "passive"))
      (node (ref "C78") (pin "1") (pinfunction "1_1") (pintype "passive"))
      (node (ref "J2") (pin "2") (pinfunction "SHIELD_2") (pintype "passive"))
      (node (ref "J3") (pin "2") (pinfunction "SHIELD_2") (pintype "passive"))
      (node (ref "J4") (pin "2") (pinfunction "SHIELD_2") (pintype "passive"))
      (node (ref "Q3") (pin "3") (pinfunction "S_3") (pintype "passive"))
      (node (ref "Q4") (pin "3") (pinfunction "S_3") (pintype "passive"))
      (node (ref "Q5") (pin "3") (pinfunction "S_3") (pintype "passive"))
      (node (ref "R120") (pin "1") (pinfunction "1_1") (pintype "passive"))
      (node (ref "R122") (pin "1") (pinfunction "1_1") (pintype "passive"))
      (node (ref "R123") (pin "1") (pinfunction "1_1") (pintype "passive"))
      (node (ref "R124") (pin "3") (pinfunction "3_3") (pintype "passive"))
      (node (ref "R127") (pin "1") (pinfunction "1_1") (pintype "passive"))
      (node (ref "R35") (pin "1") (pinfunction "1_1") (pintype "passive"))
      (node (ref "R41") (pin "1") (pinfunction "1_1") (pintype "passive"))
      (node (ref "R49") (pin "1") (pinfunction "1_1") (pintype "passive"))
      (node (ref "R50") (pin "1") (pinfunction "1_1") (pintype "passive"))
      (node (ref "SHLD3") (pin "1") (pinfunction "1_1") (pintype "passive"))
      (node (ref "U7") (pin "17") (pinfunction "PAD_17") (pintype "power_in"))
      (node (ref "U7") (pin "5") (pinfunction "GND_5") (pintype "power_in"))
      (node (ref "U7") (pin "8") (pinfunction "GND_8") (pintype "power_in"))
      (node (ref "U9") (pin "17") (pinfunction "PAD_17") (pintype "passive"))
    )
    (net (code "25") (name "Net-(C20-Pad1)") (class "Default")
      (node (ref "C20") (pin "1") (pinfunction "1_1") (pintype "passive"))
      (node (ref "K2") (pin "7") (pinfunction "7_7") (pintype "passive"))
      (node (ref "R31") (pin "2") (pinfunction "2_2") (pintype "passive"))
    )
    (net (code "26") (name "Net-(C21-Pad1)") (class "Default")
      (node (ref "C21") (pin "1") (pinfunction "1_1") (pintype "passive"))
      (node (ref "C23") (pin "2") (pinfunction "2_2") (pintype "passive"))
      (node (ref "K1") (pin "7") (pinfunction "7_7") (pintype "passive"))
      (node (ref "R33") (pin "2") (pinfunction "2_2") (pintype "passive"))
      (node (ref "R35") (pin "2") (pinfunction "2_2") (pintype "passive"))
    )
    (net (code "27") (name "Net-(C21-Pad2)") (class "Default")
      (node (ref "C21") (pin "2") (pinfunction "2_2") (pintype "passive"))
      (node (ref "C22") (pin "2") (pinfunction "2_2") (pintype "passive"))
      (node (ref "R32") (pin "1") (pinfunction "1_1") (pintype "passive"))
      (node (ref "R43") (pin "1") (pinfunction "1_1") (pintype "passive"))
    )
    (net (code "28") (name "Net-(C26-Pad2)") (class "Default")
      (node (ref "C26") (pin "2") (pinfunction "2_2") (pintype "passive"))
      (node (ref "R54") (pin "2") (pinfunction "2_2") (pintype "passive"))
    )
    (net (code "29") (name "Net-(C28-Pad1)") (class "Default")
      (node (ref "C28") (pin "1") (pinfunction "1_1") (pintype "passive"))
      (node (ref "FB4") (pin "1") (pinfunction "1_1") (pintype "passive"))
      (node (ref "R99") (pin "1") (pinfunction "1_1") (pintype "passive"))
    )
    (net (code "30") (name "Net-(D2-A)") (class "Default")
      (node (ref "D2") (pin "2") (pinfunction "A_2") (pintype "passive"))
      (node (ref "K1") (pin "8") (pinfunction "8_8") (pintype "passive"))
      (node (ref "Q3") (pin "1") (pinfunction "D_1") (pintype "passive"))
    )
    (net (code "31") (name "Net-(D3-A)") (class "Default")
      (node (ref "D3") (pin "2") (pinfunction "A_2") (pintype "passive"))
      (node (ref "K2") (pin "8") (pinfunction "8_8") (pintype "passive"))
      (node (ref "Q4") (pin "1") (pinfunction "D_1") (pintype "passive"))
    )
    (net (code "32") (name "Net-(FB6-Pad2)") (class "Default")
      (node (ref "FB6") (pin "2") (pinfunction "2_2") (pintype "passive"))
      (node (ref "R118") (pin "2") (pinfunction "2_2") (pintype "passive"))
      (node (ref "R119") (pin "1") (pinfunction "1_1") (pintype "passive"))
    )
    (net (code "33") (name "Net-(J2-Signal)") (class "Default")
      (node (ref "J2") (pin "1") (pinfunction "Signal_1") (pintype "passive"))
      (node (ref "K1") (pin "3") (pinfunction "3_3") (pintype "passive"))
    )
    (net (code "34") (name "Net-(K1-Pad2)") (class "Default")
      (node (ref "K1") (pin "2") (pinfunction "2_2") (pintype "passive"))
      (node (ref "R43") (pin "2") (pinfunction "2_2") (pintype "passive"))
    )
    (net (code "35") (name "Net-(K1-Pad4)") (class "Default")
      (node (ref "K1") (pin "4") (pinfunction "4_4") (pintype "passive"))
      (node (ref "K1") (pin "5") (pinfunction "5_5") (pintype "passive"))
    )
    (net (code "36") (name "Net-(K1-Pad6)") (class "Default")
      (node (ref "K1") (pin "6") (pinfunction "6_6") (pintype "passive"))
      (node (ref "K2") (pin "3") (pinfunction "3_3") (pintype "passive"))
    )
    (net (code "37") (name "Net-(K2-Pad2)") (class "Default")
      (node (ref "K2") (pin "2") (pinfunction "2_2") (pintype "passive"))
      (node (ref "R31") (pin "1") (pinfunction "1_1") (pintype "passive"))
    )
    (net (code "38") (name "Net-(K2-Pad4)") (class "Default")
      (node (ref "K2") (pin "4") (pinfunction "4_4") (pintype "passive"))
      (node (ref "R30") (pin "1") (pinfunction "1_1") (pintype "passive"))
    )
    (net (code "39") (name "Net-(K2-Pad5)") (class "Default")
      (node (ref "K2") (pin "5") (pinfunction "5_5") (pintype "passive"))
      (node (ref "R29") (pin "2") (pinfunction "2_2") (pintype "passive"))
      (node (ref "R41") (pin "2") (pinfunction "2_2") (pintype "passive"))
    )
    (net (code "40") (name "Net-(Q3-G)") (class "Default")
      (node (ref "Q3") (pin "2") (pinfunction "G_2") (pintype "passive"))
      (node (ref "R47") (pin "1") (pinfunction "1_1") (pintype "passive"))
    )
    (net (code "41") (name "Net-(Q4-G)") (class "Default")
      (node (ref "Q4") (pin "2") (pinfunction "G_2") (pintype "passive"))
      (node (ref "R48") (pin "1") (pinfunction "1_1") (pintype "passive"))
    )
    (net (code "42") (name "Net-(Q5-G)") (class "Default")
      (node (ref "Q5") (pin "2") (pinfunction "G_2") (pintype "passive"))
      (node (ref "R126") (pin "1") (pinfunction "1_1") (pintype "passive"))
    )
    (net (code "43") (name "Net-(R29-Pad1)") (class "Default")
      (node (ref "R29") (pin "1") (pinfunction "1_1") (pintype "passive"))
      (node (ref "R30") (pin "2") (pinfunction "2_2") (pintype "passive"))
    )
    (net (code "44") (name "Net-(R32-Pad2)") (class "Default")
      (node (ref "R32") (pin "2") (pinfunction "2_2") (pintype "passive"))
      (node (ref "R33") (pin "1") (pinfunction "1_1") (pintype "passive"))
    )
    (net (code "45") (name "Net-(R53-Pad2)") (class "Default")
      (node (ref "R53") (pin "2") (pinfunction "2_2") (pintype "passive"))
      (node (ref "R54") (pin "1") (pinfunction "1_1") (pintype "passive"))
    )
    (net (code "46") (name "Net-(R121-Pad1)") (class "Default")
      (node (ref "R121") (pin "1") (pinfunction "1_1") (pintype "passive"))
      (node (ref "R123") (pin "2") (pinfunction "2_2") (pintype "passive"))
      (node (ref "R124") (pin "2") (pinfunction "2_2") (pintype "passive"))
    )
    (net (code "47") (name "Net-(U7-IN_N)") (class "Default")
      (node (ref "C31") (pin "1") (pinfunction "1_1") (pintype "passive"))
      (node (ref "FB7") (pin "2") (pinfunction "2_2") (pintype "passive"))
      (node (ref "R118") (pin "1") (pinfunction "1_1") (pintype "passive"))
      (node (ref "R119") (pin "2") (pinfunction "2_2") (pintype "passive"))
      (node (ref "TP25") (pin "1") (pinfunction "1_1") (pintype "passive"))
      (node (ref "U7") (pin "7") (pinfunction "IN_N_7") (pintype "passive"))
    )
    (net (code "48") (name "Net-(U7-IN_P)") (class "Default")
      (node (ref "R56") (pin "2") (pinfunction "2_2") (pintype "passive"))
      (node (ref "U7") (pin "6") (pinfunction "IN_P_6") (pintype "passive"))
    )
    (net (code "49") (name "Net-(U9-CLL)") (class "Default")
      (node (ref "R120") (pin "2") (pinfunction "2_2") (pintype "passive"))
      (node (ref "U9") (pin "14") (pinfunction "CLL_14") (pintype "passive"))
    )
    (net (code "50") (name "Net-(U9-IN)") (class "Default")
      (node (ref "C26") (pin "1") (pinfunction "1_1") (pintype "passive"))
      (node (ref "R65") (pin "2") (pinfunction "2_2") (pintype "passive"))
      (node (ref "U9") (pin "2") (pinfunction "IN_2") (pintype "passive"))
    )
    (net (code "51") (name "Net-(U9-IN_Aux)") (class "Default")
      (node (ref "C29") (pin "2") (pinfunction "2_2") (pintype "passive"))
      (node (ref "R100") (pin "1") (pinfunction "1_1") (pintype "passive"))
      (node (ref "U9") (pin "4") (pinfunction "IN_Aux_4") (pintype "passive"))
    )
    (net (code "52") (name "Net-(U9-IN_Bias)") (class "Default")
      (node (ref "R65") (pin "1") (pinfunction "1_1") (pintype "passive"))
      (node (ref "U9") (pin "3") (pinfunction "IN_Bias_3") (pintype "passive"))
    )
    (net (code "53") (name "Net-(U9-OUT)") (class "Default")
      (node (ref "R56") (pin "1") (pinfunction "1_1") (pintype "passive"))
      (node (ref "R98") (pin "2") (pinfunction "2_2") (pintype "passive"))
      (node (ref "U9") (pin "11") (pinfunction "OUT_11") (pintype "passive"))
    )
    (net (code "54") (name "Net-(U9-R_Bias)") (class "Default")
      (node (ref "R55") (pin "1") (pinfunction "1_1") (pintype "passive"))
      (node (ref "U9") (pin "7") (pinfunction "R_Bias_7") (pintype "passive"))
    )
    (net (code "55") (name "Net-(U10-COM)") (class "Default")
      (node (ref "C27") (pin "2") (pinfunction "2_2") (pintype "passive"))
      (node (ref "R122") (pin "2") (pinfunction "2_2") (pintype "passive"))
      (node (ref "U10") (pin "1") (pinfunction "COM_1") (pintype "passive"))
      (node (ref "U18") (pin "3") (pinfunction "+_3") (pintype "passive"))
    )
    (net (code "56") (name "Net-(U10-NO)") (class "Default")
      (node (ref "C27") (pin "1") (pinfunction "1_1") (pintype "passive"))
      (node (ref "R96") (pin "1") (pinfunction "1_1") (pintype "passive"))
      (node (ref "U10") (pin "2") (pinfunction "NO_2") (pintype "passive"))
    )
    (net (code "57") (name "Net-(U18--)") (class "Default")
      (node (ref "C30") (pin "2") (pinfunction "2_2") (pintype "passive"))
      (node (ref "R121") (pin "2") (pinfunction "2_2") (pintype "passive"))
      (node (ref "R98") (pin "1") (pinfunction "1_1") (pintype "passive"))
      (node (ref "R99") (pin "2") (pinfunction "2_2") (pintype "passive"))
      (node (ref "U18") (pin "2") (pinfunction "-_2") (pintype "passive"))
    )
    (net (code "58") (name "Net-(U18-OUT)") (class "Default")
      (node (ref "C30") (pin "1") (pinfunction "1_1") (pintype "passive"))
      (node (ref "R100") (pin "2") (pinfunction "2_2") (pintype "passive"))
      (node (ref "U18") (pin "6") (pinfunction "OUT_6") (pintype "passive"))
    )
    (net (code "59") (name "unconnected-(R124-Pad1)") (class "Default")
      (node (ref "R124") (pin "1") (pinfunction "1_1") (pintype "passive+no_connect"))
    )
    (net (code "60") (name "unconnected-(U7-AUX_N-Pad2)") (class "Default")
      (node (ref "U7") (pin "2") (pinfunction "AUX_N_2") (pintype "passive+no_connect"))
    )
    (net (code "61") (name "unconnected-(U7-AUX_P-Pad1)") (class "Default")
      (node (ref "U7") (pin "1") (pinfunction "AUX_P_1") (pintype "passive+no_connect"))
    )
    (net (code "62") (name "unconnected-(U7-AUX_VCM-Pad16)") (class "Default")
      (node (ref "U7") (pin "16") (pinfunction "AUX_VCM_16") (pintype "input+no_connect"))
    )
    (net (code "63") (name "unconnected-(U9-NC-Pad9)") (class "Default")
      (node (ref "U9") (pin "9") (pinfunction "NC_9") (pintype "passive+no_connect"))
    )
    (net (code "64") (name "unconnected-(U9-NC-Pad13)") (class "Default")
      (node (ref "U9") (pin "13") (pinfunction "NC_13") (pintype "passive+no_connect"))
    )
    (net (code "65") (name "unconnected-(U9-NC-Pad16)") (class "Default")
      (node (ref "U9") (pin "16") (pinfunction "NC_16") (pintype "passive+no_connect"))
    )
    (net (code "66") (name "unconnected-(U18-N1-Pad1)") (class "Default")
      (node (ref "U18") (pin "1") (pinfunction "N1_1") (pintype "passive+no_connect"))
    )
    (net (code "67") (name "unconnected-(U18-N2-Pad8)") (class "Default")
      (node (ref "U18") (pin "8") (pinfunction "N2_8") (pintype "passive+no_connect"))
    )
  )
)
